# FEP.net
KiCad netlist of a schematic drawn in EAGLE
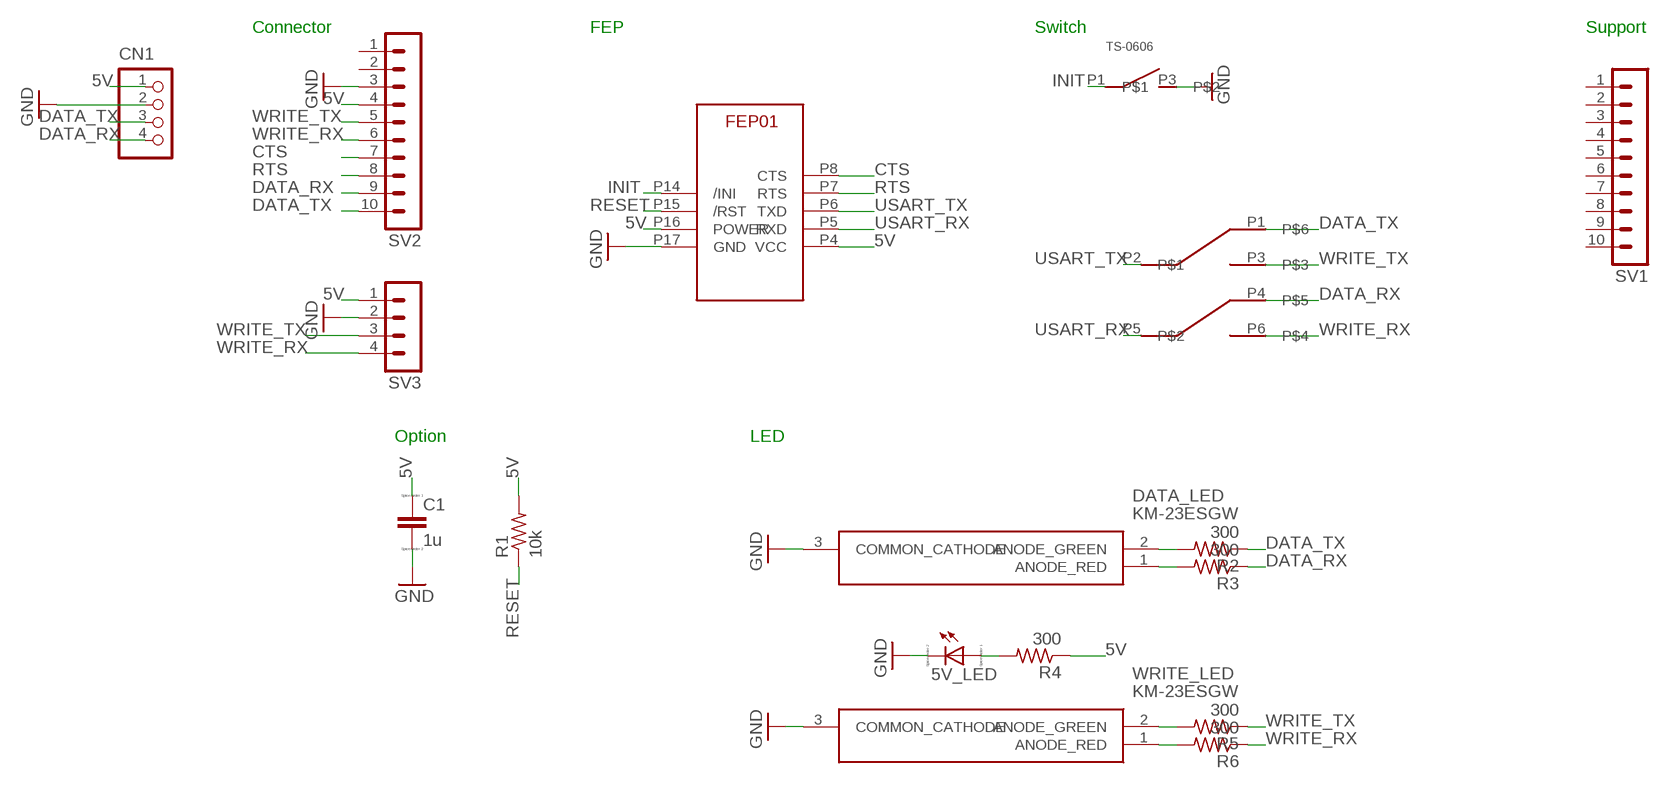
[diagram p0: schematic, sheet 1]

(export (version "E")
  (design (tool "Eeschema 10.0.6"))
  (components
    (comp (ref "5V_LED")
      (value "LED_E")
      (footprint "eagle-import:LED_1206")
      (libsource (lib "eagle-import") (part "LED_E"))
    )
    (comp (ref "C1")
      (value "1u")
      (footprint "eagle-import:C0603")
      (libsource (lib "eagle-import") (part "CC0603"))
    )
    (comp (ref "CN1")
      (value "S4B-XASK-1")
      (footprint "eagle-import:S4B-XASK-1")
      (libsource (lib "eagle-import") (part "S4B-XASK-1"))
    )
    (comp (ref "DATA_LED")
      (value "KM-23ESGW")
      (footprint "eagle-import:SOT-23")
      (libsource (lib "eagle-import") (part "KM-23ESGW"))
    )
    (comp (ref "FEP_1")
      (value "FEP01")
      (footprint "eagle-import:FEP01")
      (libsource (lib "eagle-import") (part "FEP01"))
    )
    (comp (ref "R1")
      (value "10k")
      (footprint "eagle-import:R0603")
      (libsource (lib "eagle-import") (part "R-US_R0603"))
    )
    (comp (ref "R2")
      (value "300")
      (footprint "eagle-import:R0603")
      (libsource (lib "eagle-import") (part "R-US_R0603"))
    )
    (comp (ref "R3")
      (value "300")
      (footprint "eagle-import:R0603")
      (libsource (lib "eagle-import") (part "R-US_R0603"))
    )
    (comp (ref "R4")
      (value "300")
      (footprint "eagle-import:R0603")
      (libsource (lib "eagle-import") (part "R-US_R0603"))
    )
    (comp (ref "R5")
      (value "300")
      (footprint "eagle-import:R0603")
      (libsource (lib "eagle-import") (part "R-US_R0603"))
    )
    (comp (ref "R6")
      (value "300")
      (footprint "eagle-import:R0603")
      (libsource (lib "eagle-import") (part "R-US_R0603"))
    )
    (comp (ref "SV1")
      (value "MA10-1")
      (footprint "eagle-import:MA10-1")
      (libsource (lib "eagle-import") (part "MA10-1"))
    )
    (comp (ref "SV2")
      (value "MA10-1")
      (footprint "eagle-import:MA10-1")
      (libsource (lib "eagle-import") (part "MA10-1"))
    )
    (comp (ref "SV3")
      (value "MA04-1")
      (footprint "eagle-import:MA04-1")
      (libsource (lib "eagle-import") (part "MA04-1"))
    )
    (comp (ref "SW_1")
      (value "P-03647_TS-0606")
      (footprint "eagle-import:TS-0606")
      (libsource (lib "eagle-import") (part "P-03647_TS-0606"))
    )
    (comp (ref "SW_3")
      (value "P-08784_PS-70S")
      (footprint "eagle-import:PS-70S")
      (libsource (lib "eagle-import") (part "P-08784_PS-70S"))
    )
    (comp (ref "WRITE_LED")
      (value "KM-23ESGW")
      (footprint "eagle-import:SOT-23")
      (libsource (lib "eagle-import") (part "KM-23ESGW"))
    )
  )
  (nets
    (net (code "1") (name "/5V") (class "Default")
      (node (ref "C1") (pin "1") (pinfunction "1_1") (pintype "passive"))
      (node (ref "CN1") (pin "1") (pinfunction "1_1") (pintype "passive"))
      (node (ref "FEP_1") (pin "P16") (pinfunction "POWER_P16") (pintype "bidirectional"))
      (node (ref "FEP_1") (pin "P4") (pinfunction "VCC_P4") (pintype "bidirectional"))
      (node (ref "R1") (pin "2") (pinfunction "2_2") (pintype "passive"))
      (node (ref "R4") (pin "1") (pinfunction "1_1") (pintype "passive"))
      (node (ref "SV2") (pin "4") (pinfunction "4_4") (pintype "passive"))
      (node (ref "SV3") (pin "1") (pinfunction "1_1") (pintype "passive"))
    )
    (net (code "2") (name "/CTS") (class "Default")
      (node (ref "FEP_1") (pin "P8") (pinfunction "CTS_P8") (pintype "bidirectional"))
      (node (ref "SV2") (pin "7") (pinfunction "7_7") (pintype "passive"))
    )
    (net (code "3") (name "/DATA_RX") (class "Default")
      (node (ref "CN1") (pin "4") (pinfunction "4_4") (pintype "passive"))
      (node (ref "R3") (pin "1") (pinfunction "1_1") (pintype "passive"))
      (node (ref "SV2") (pin "9") (pinfunction "9_9") (pintype "passive"))
      (node (ref "SW_3") (pin "P4") (pinfunction "P$5_P4") (pintype "bidirectional"))
    )
    (net (code "4") (name "/DATA_TX") (class "Default")
      (node (ref "CN1") (pin "3") (pinfunction "3_3") (pintype "passive"))
      (node (ref "R2") (pin "1") (pinfunction "1_1") (pintype "passive"))
      (node (ref "SV2") (pin "10") (pinfunction "10_10") (pintype "passive"))
      (node (ref "SW_3") (pin "P1") (pinfunction "P$6_P1") (pintype "bidirectional"))
    )
    (net (code "5") (name "/INIT") (class "Default")
      (node (ref "FEP_1") (pin "P14") (pinfunction "/INI_P14") (pintype "bidirectional"))
      (node (ref "SW_1") (pin "P1") (pinfunction "P$1_P1") (pintype "bidirectional"))
    )
    (net (code "6") (name "/RESET") (class "Default")
      (node (ref "FEP_1") (pin "P15") (pinfunction "/RST_P15") (pintype "bidirectional"))
      (node (ref "R1") (pin "1") (pinfunction "1_1") (pintype "passive"))
    )
    (net (code "7") (name "/RTS") (class "Default")
      (node (ref "FEP_1") (pin "P7") (pinfunction "RTS_P7") (pintype "bidirectional"))
      (node (ref "SV2") (pin "8") (pinfunction "8_8") (pintype "passive"))
    )
    (net (code "8") (name "/USART_RX") (class "Default")
      (node (ref "FEP_1") (pin "P5") (pinfunction "RXD_P5") (pintype "bidirectional"))
      (node (ref "SW_3") (pin "P5") (pinfunction "P$2_P5") (pintype "bidirectional"))
    )
    (net (code "9") (name "/USART_TX") (class "Default")
      (node (ref "FEP_1") (pin "P6") (pinfunction "TXD_P6") (pintype "bidirectional"))
      (node (ref "SW_3") (pin "P2") (pinfunction "P$1_P2") (pintype "bidirectional"))
    )
    (net (code "10") (name "/WRITE_RX") (class "Default")
      (node (ref "R6") (pin "1") (pinfunction "1_1") (pintype "passive"))
      (node (ref "SV2") (pin "6") (pinfunction "6_6") (pintype "passive"))
      (node (ref "SV3") (pin "4") (pinfunction "4_4") (pintype "passive"))
      (node (ref "SW_3") (pin "P6") (pinfunction "P$4_P6") (pintype "bidirectional"))
    )
    (net (code "11") (name "/WRITE_TX") (class "Default")
      (node (ref "R5") (pin "1") (pinfunction "1_1") (pintype "passive"))
      (node (ref "SV2") (pin "5") (pinfunction "5_5") (pintype "passive"))
      (node (ref "SV3") (pin "3") (pinfunction "3_3") (pintype "passive"))
      (node (ref "SW_3") (pin "P3") (pinfunction "P$3_P3") (pintype "bidirectional"))
    )
    (net (code "12") (name "GND") (class "Default")
      (node (ref "5V_LED") (pin "C") (pinfunction "C_C") (pintype "passive"))
      (node (ref "C1") (pin "2") (pinfunction "2_2") (pintype "passive"))
      (node (ref "CN1") (pin "2") (pinfunction "2_2") (pintype "passive"))
      (node (ref "DATA_LED") (pin "3") (pinfunction "COMMON_CATHODE_3") (pintype "bidirectional"))
      (node (ref "FEP_1") (pin "P17") (pinfunction "GND_P17") (pintype "bidirectional"))
      (node (ref "SV2") (pin "3") (pinfunction "3_3") (pintype "passive"))
      (node (ref "SV3") (pin "2") (pinfunction "2_2") (pintype "passive"))
      (node (ref "SW_1") (pin "P3") (pinfunction "P$2_P3") (pintype "bidirectional"))
      (node (ref "WRITE_LED") (pin "3") (pinfunction "COMMON_CATHODE_3") (pintype "bidirectional"))
    )
    (net (code "13") (name "Net-(5V_LED-PadA)") (class "Default")
      (node (ref "5V_LED") (pin "A") (pinfunction "A_A") (pintype "passive"))
      (node (ref "R4") (pin "2") (pinfunction "2_2") (pintype "passive"))
    )
    (net (code "14") (name "Net-(DATA_LED-ANODE_GREEN)") (class "Default")
      (node (ref "DATA_LED") (pin "2") (pinfunction "ANODE_GREEN_2") (pintype "bidirectional"))
      (node (ref "R2") (pin "2") (pinfunction "2_2") (pintype "passive"))
    )
    (net (code "15") (name "Net-(DATA_LED-ANODE_RED)") (class "Default")
      (node (ref "DATA_LED") (pin "1") (pinfunction "ANODE_RED_1") (pintype "bidirectional"))
      (node (ref "R3") (pin "2") (pinfunction "2_2") (pintype "passive"))
    )
    (net (code "16") (name "Net-(WRITE_LED-ANODE_GREEN)") (class "Default")
      (node (ref "R5") (pin "2") (pinfunction "2_2") (pintype "passive"))
      (node (ref "WRITE_LED") (pin "2") (pinfunction "ANODE_GREEN_2") (pintype "bidirectional"))
    )
    (net (code "17") (name "Net-(WRITE_LED-ANODE_RED)") (class "Default")
      (node (ref "R6") (pin "2") (pinfunction "2_2") (pintype "passive"))
      (node (ref "WRITE_LED") (pin "1") (pinfunction "ANODE_RED_1") (pintype "bidirectional"))
    )
    (net (code "18") (name "unconnected-(SV1-Pad1)") (class "Default")
      (node (ref "SV1") (pin "1") (pinfunction "1_1") (pintype "passive"))
    )
    (net (code "19") (name "unconnected-(SV1-Pad2)") (class "Default")
      (node (ref "SV1") (pin "2") (pinfunction "2_2") (pintype "passive"))
    )
    (net (code "20") (name "unconnected-(SV1-Pad3)") (class "Default")
      (node (ref "SV1") (pin "3") (pinfunction "3_3") (pintype "passive"))
    )
    (net (code "21") (name "unconnected-(SV1-Pad4)") (class "Default")
      (node (ref "SV1") (pin "4") (pinfunction "4_4") (pintype "passive"))
    )
    (net (code "22") (name "unconnected-(SV1-Pad5)") (class "Default")
      (node (ref "SV1") (pin "5") (pinfunction "5_5") (pintype "passive"))
    )
    (net (code "23") (name "unconnected-(SV1-Pad6)") (class "Default")
      (node (ref "SV1") (pin "6") (pinfunction "6_6") (pintype "passive"))
    )
    (net (code "24") (name "unconnected-(SV1-Pad7)") (class "Default")
      (node (ref "SV1") (pin "7") (pinfunction "7_7") (pintype "passive"))
    )
    (net (code "25") (name "unconnected-(SV1-Pad8)") (class "Default")
      (node (ref "SV1") (pin "8") (pinfunction "8_8") (pintype "passive"))
    )
    (net (code "26") (name "unconnected-(SV1-Pad9)") (class "Default")
      (node (ref "SV1") (pin "9") (pinfunction "9_9") (pintype "passive"))
    )
    (net (code "27") (name "unconnected-(SV1-Pad10)") (class "Default")
      (node (ref "SV1") (pin "10") (pinfunction "10_10") (pintype "passive"))
    )
    (net (code "28") (name "unconnected-(SV2-Pad1)") (class "Default")
      (node (ref "SV2") (pin "1") (pinfunction "1_1") (pintype "passive"))
    )
    (net (code "29") (name "unconnected-(SV2-Pad2)") (class "Default")
      (node (ref "SV2") (pin "2") (pinfunction "2_2") (pintype "passive"))
    )
  )
)
